# IMU.net
KiCad netlist of a schematic drawn in Altium Designer
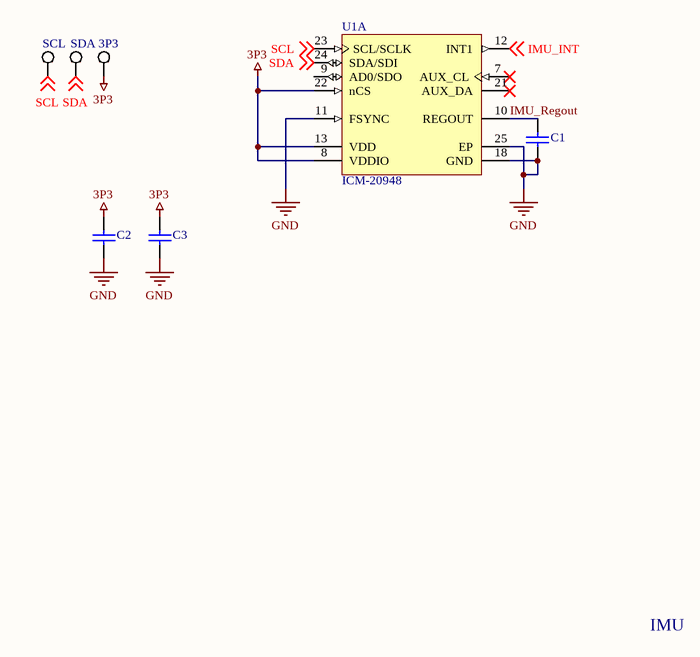
[diagram p0: IMU.SchDoc]

(export (version "E")
  (design (tool "Eeschema 10.0.6"))
  (components
    (comp (ref "3P3")
      (value "5019")
      (footprint "KSTN-5019_V")
      (description "Test Point, 1 Position SMD, RoHS, Tape and Reel")
      (libsource (lib "Altium Content Vault") (part "TESTPOINT_WHITE"))
    )
    (comp (ref "C1")
      (value "GRM21BR71H104KA01L")
      (footprint "CAPC2013X135X45ML10T25")
      (description "Chip Capacitor, 0.1 uF, +/- 10%, 50 V, -55 to 125 degC, 0805 (2012 Metric), RoHS, Tape and Reel")
      (fields (field (name "VOLTAGE") "50V") (field (name "TOLERANCE") "10%"))
      (libsource (lib "Altium Content Vault") (part "CAP-NP-2"))
    )
    (comp (ref "C2")
      (value "GRM21BR71H104KA01L")
      (footprint "CAPC2013X135X45ML10T25")
      (description "Chip Capacitor, 0.1 uF, +/- 10%, 50 V, -55 to 125 degC, 0805 (2012 Metric), RoHS, Tape and Reel")
      (fields (field (name "VOLTAGE") "50V") (field (name "TOLERANCE") "10%"))
      (libsource (lib "Altium Content Vault") (part "CAP-NP-2"))
    )
    (comp (ref "C3")
      (value "GRM21BR71H104KA01L")
      (footprint "CAPC2013X135X45ML10T25")
      (description "Chip Capacitor, 0.1 uF, +/- 10%, 50 V, -55 to 125 degC, 0805 (2012 Metric), RoHS, Tape and Reel")
      (fields (field (name "VOLTAGE") "50V") (field (name "TOLERANCE") "10%"))
      (libsource (lib "Altium Content Vault") (part "CAP-NP-2"))
    )
    (comp (ref "SCL")
      (value "5019")
      (footprint "KSTN-5019_V")
      (description "Test Point, 1 Position SMD, RoHS, Tape and Reel")
      (libsource (lib "Altium Content Vault") (part "TESTPOINT_WHITE"))
    )
    (comp (ref "SDA")
      (value "5019")
      (footprint "KSTN-5019_V")
      (description "Test Point, 1 Position SMD, RoHS, Tape and Reel")
      (libsource (lib "Altium Content Vault") (part "TESTPOINT_WHITE"))
    )
    (comp (ref "U1")
      (value "ICM-20948")
      (footprint "TDK-QFN-24_L")
      (fields (field (name "MANUFACTURER") "TDK"))
      (libsource (lib "Altium Content Vault") (part "TDK-ICM-20948-QFN-24"))
    )
  )
  (nets
    (net (code "1") (name "/IMU_Regout") (class "Default")
      (node (ref "C1") (pin "2") (pinfunction "2_2") (pintype "passive"))
      (node (ref "U1") (pin "10") (pinfunction "REGOUT_10") (pintype "passive"))
    )
    (net (code "2") (name "3P3") (class "Default")
      (node (ref "3P3") (pin "1") (pinfunction "1_1") (pintype "passive"))
      (node (ref "C2") (pin "2") (pinfunction "2_2") (pintype "passive"))
      (node (ref "C3") (pin "2") (pinfunction "2_2") (pintype "passive"))
      (node (ref "U1") (pin "13") (pinfunction "VDD_13") (pintype "power_in"))
      (node (ref "U1") (pin "22") (pinfunction "nCS_22") (pintype "input"))
      (node (ref "U1") (pin "8") (pinfunction "VDDIO_8") (pintype "power_in"))
    )
    (net (code "3") (name "GND") (class "Default")
      (node (ref "C1") (pin "1") (pinfunction "1_1") (pintype "passive"))
      (node (ref "C2") (pin "1") (pinfunction "1_1") (pintype "passive"))
      (node (ref "C3") (pin "1") (pinfunction "1_1") (pintype "passive"))
      (node (ref "U1") (pin "11") (pinfunction "FSYNC_11") (pintype "input"))
      (node (ref "U1") (pin "18") (pinfunction "GND_18") (pintype "power_in"))
      (node (ref "U1") (pin "25") (pinfunction "EP_25") (pintype "passive"))
    )
    (net (code "4") (name "IMU_INT") (class "Default")
      (node (ref "U1") (pin "12") (pinfunction "INT1_12") (pintype "output"))
    )
    (net (code "5") (name "SCL") (class "Default")
      (node (ref "SCL") (pin "1") (pinfunction "1_1") (pintype "passive"))
      (node (ref "U1") (pin "23") (pinfunction "SCL/SCLK_23") (pintype "input"))
    )
    (net (code "6") (name "SDA") (class "Default")
      (node (ref "SDA") (pin "1") (pinfunction "1_1") (pintype "passive"))
      (node (ref "U1") (pin "24") (pinfunction "SDA/SDI_24") (pintype "bidirectional"))
    )
    (net (code "7") (name "unconnected-(U1A-AD0{slash}SDO-Pad9)") (class "Default")
      (node (ref "U1") (pin "9") (pinfunction "AD0/SDO_9") (pintype "bidirectional"))
    )
    (net (code "8") (name "unconnected-(U1A-AUX_CL-Pad7)") (class "Default")
      (node (ref "U1") (pin "7") (pinfunction "AUX_CL_7") (pintype "input+no_connect"))
    )
    (net (code "9") (name "unconnected-(U1A-AUX_DA-Pad21)") (class "Default")
      (node (ref "U1") (pin "21") (pinfunction "AUX_DA_21") (pintype "passive+no_connect"))
    )
  )
)
